# ProDoc_Home_Automation_Device_2026-02-15.net
KiCad netlist of a schematic drawn in EasyEDA Pro
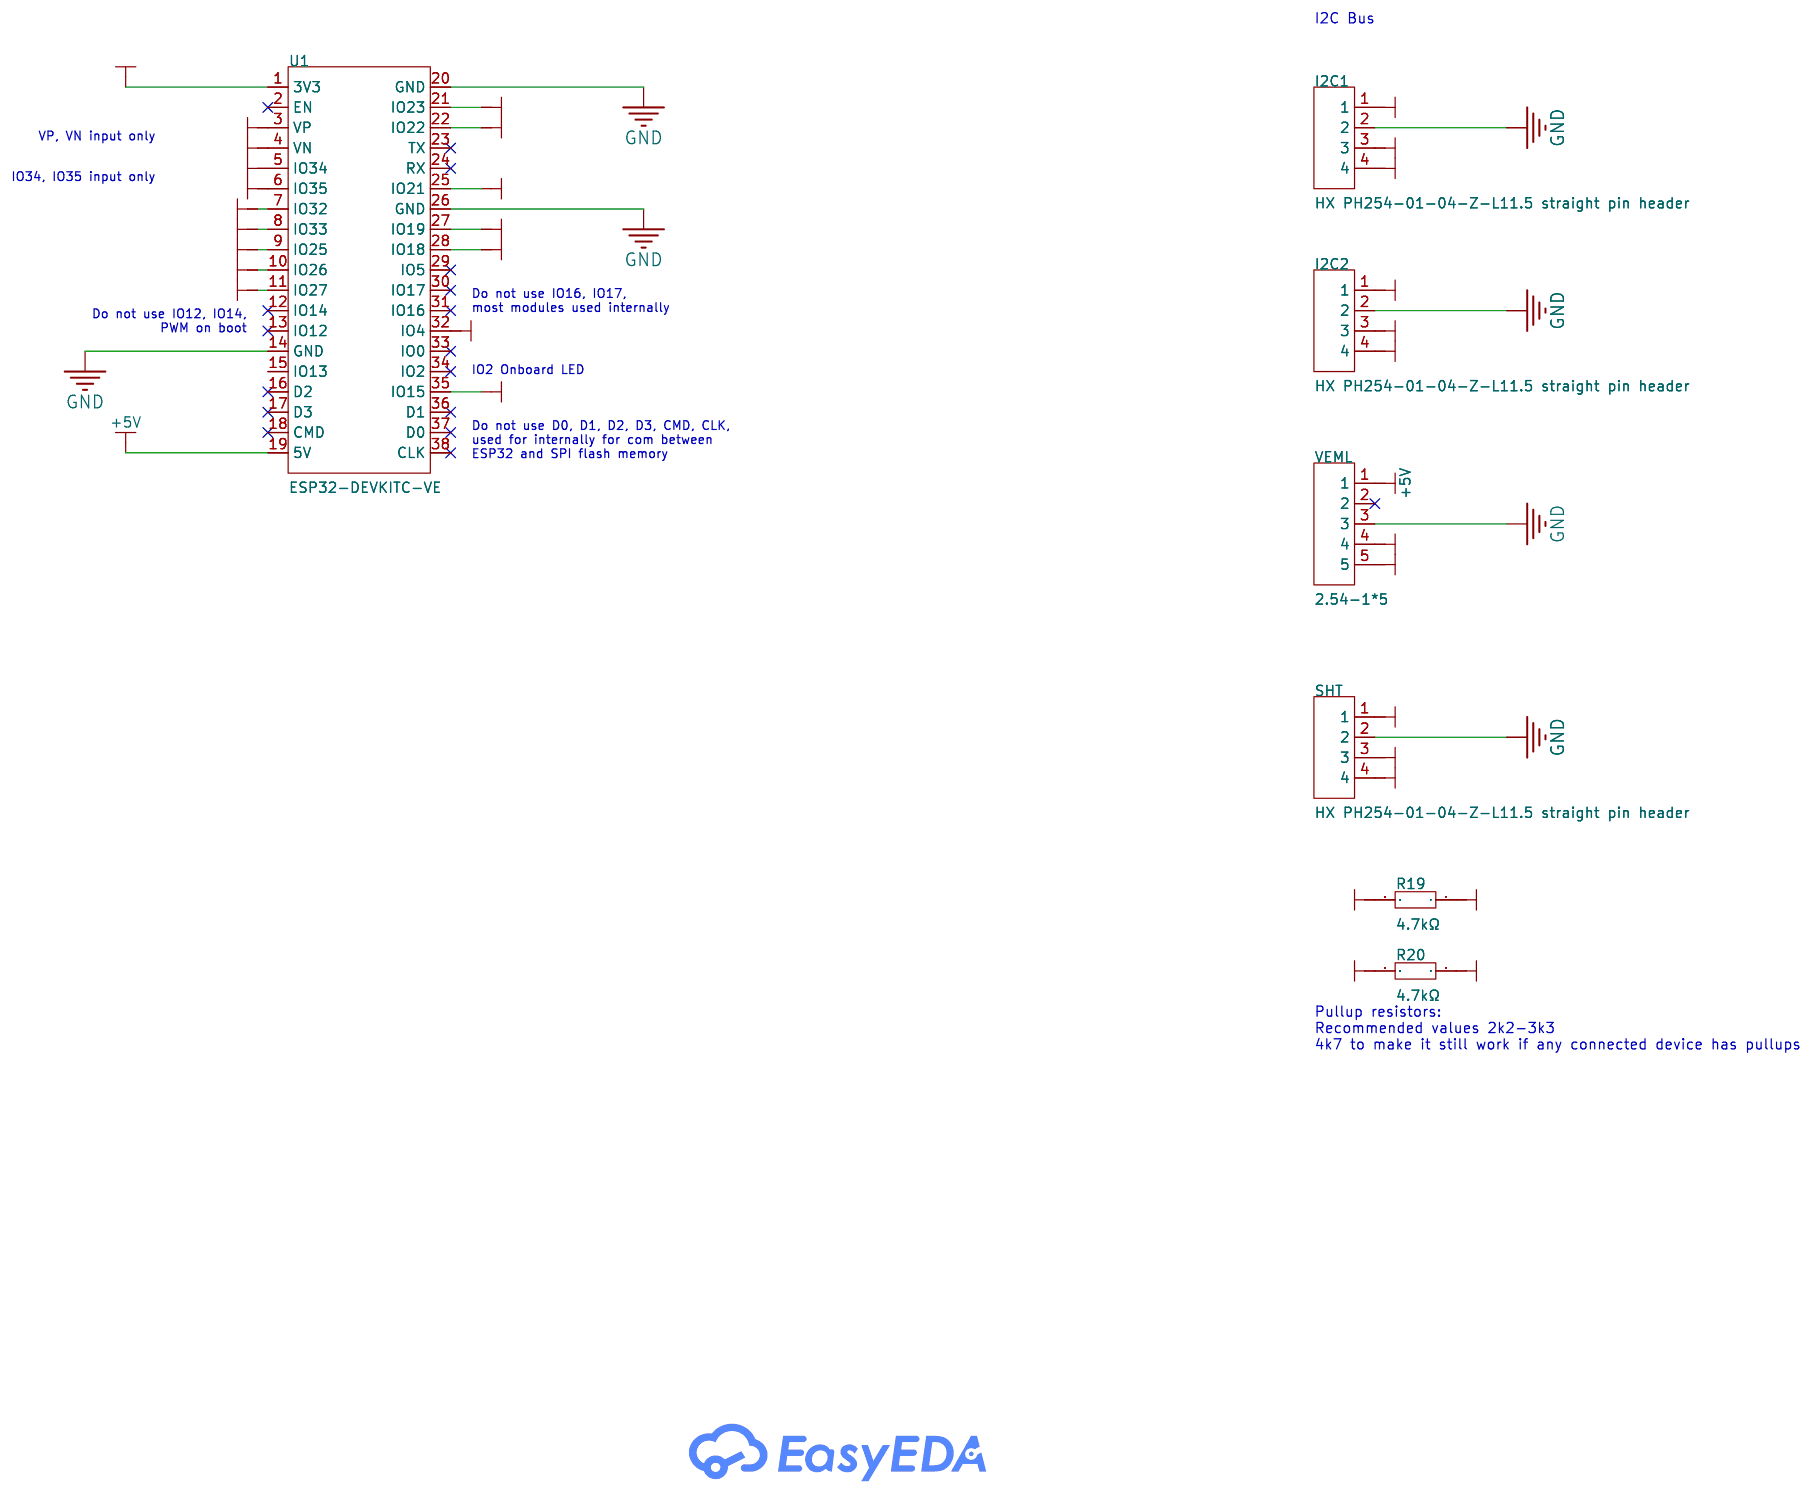
[diagram p0: Main]
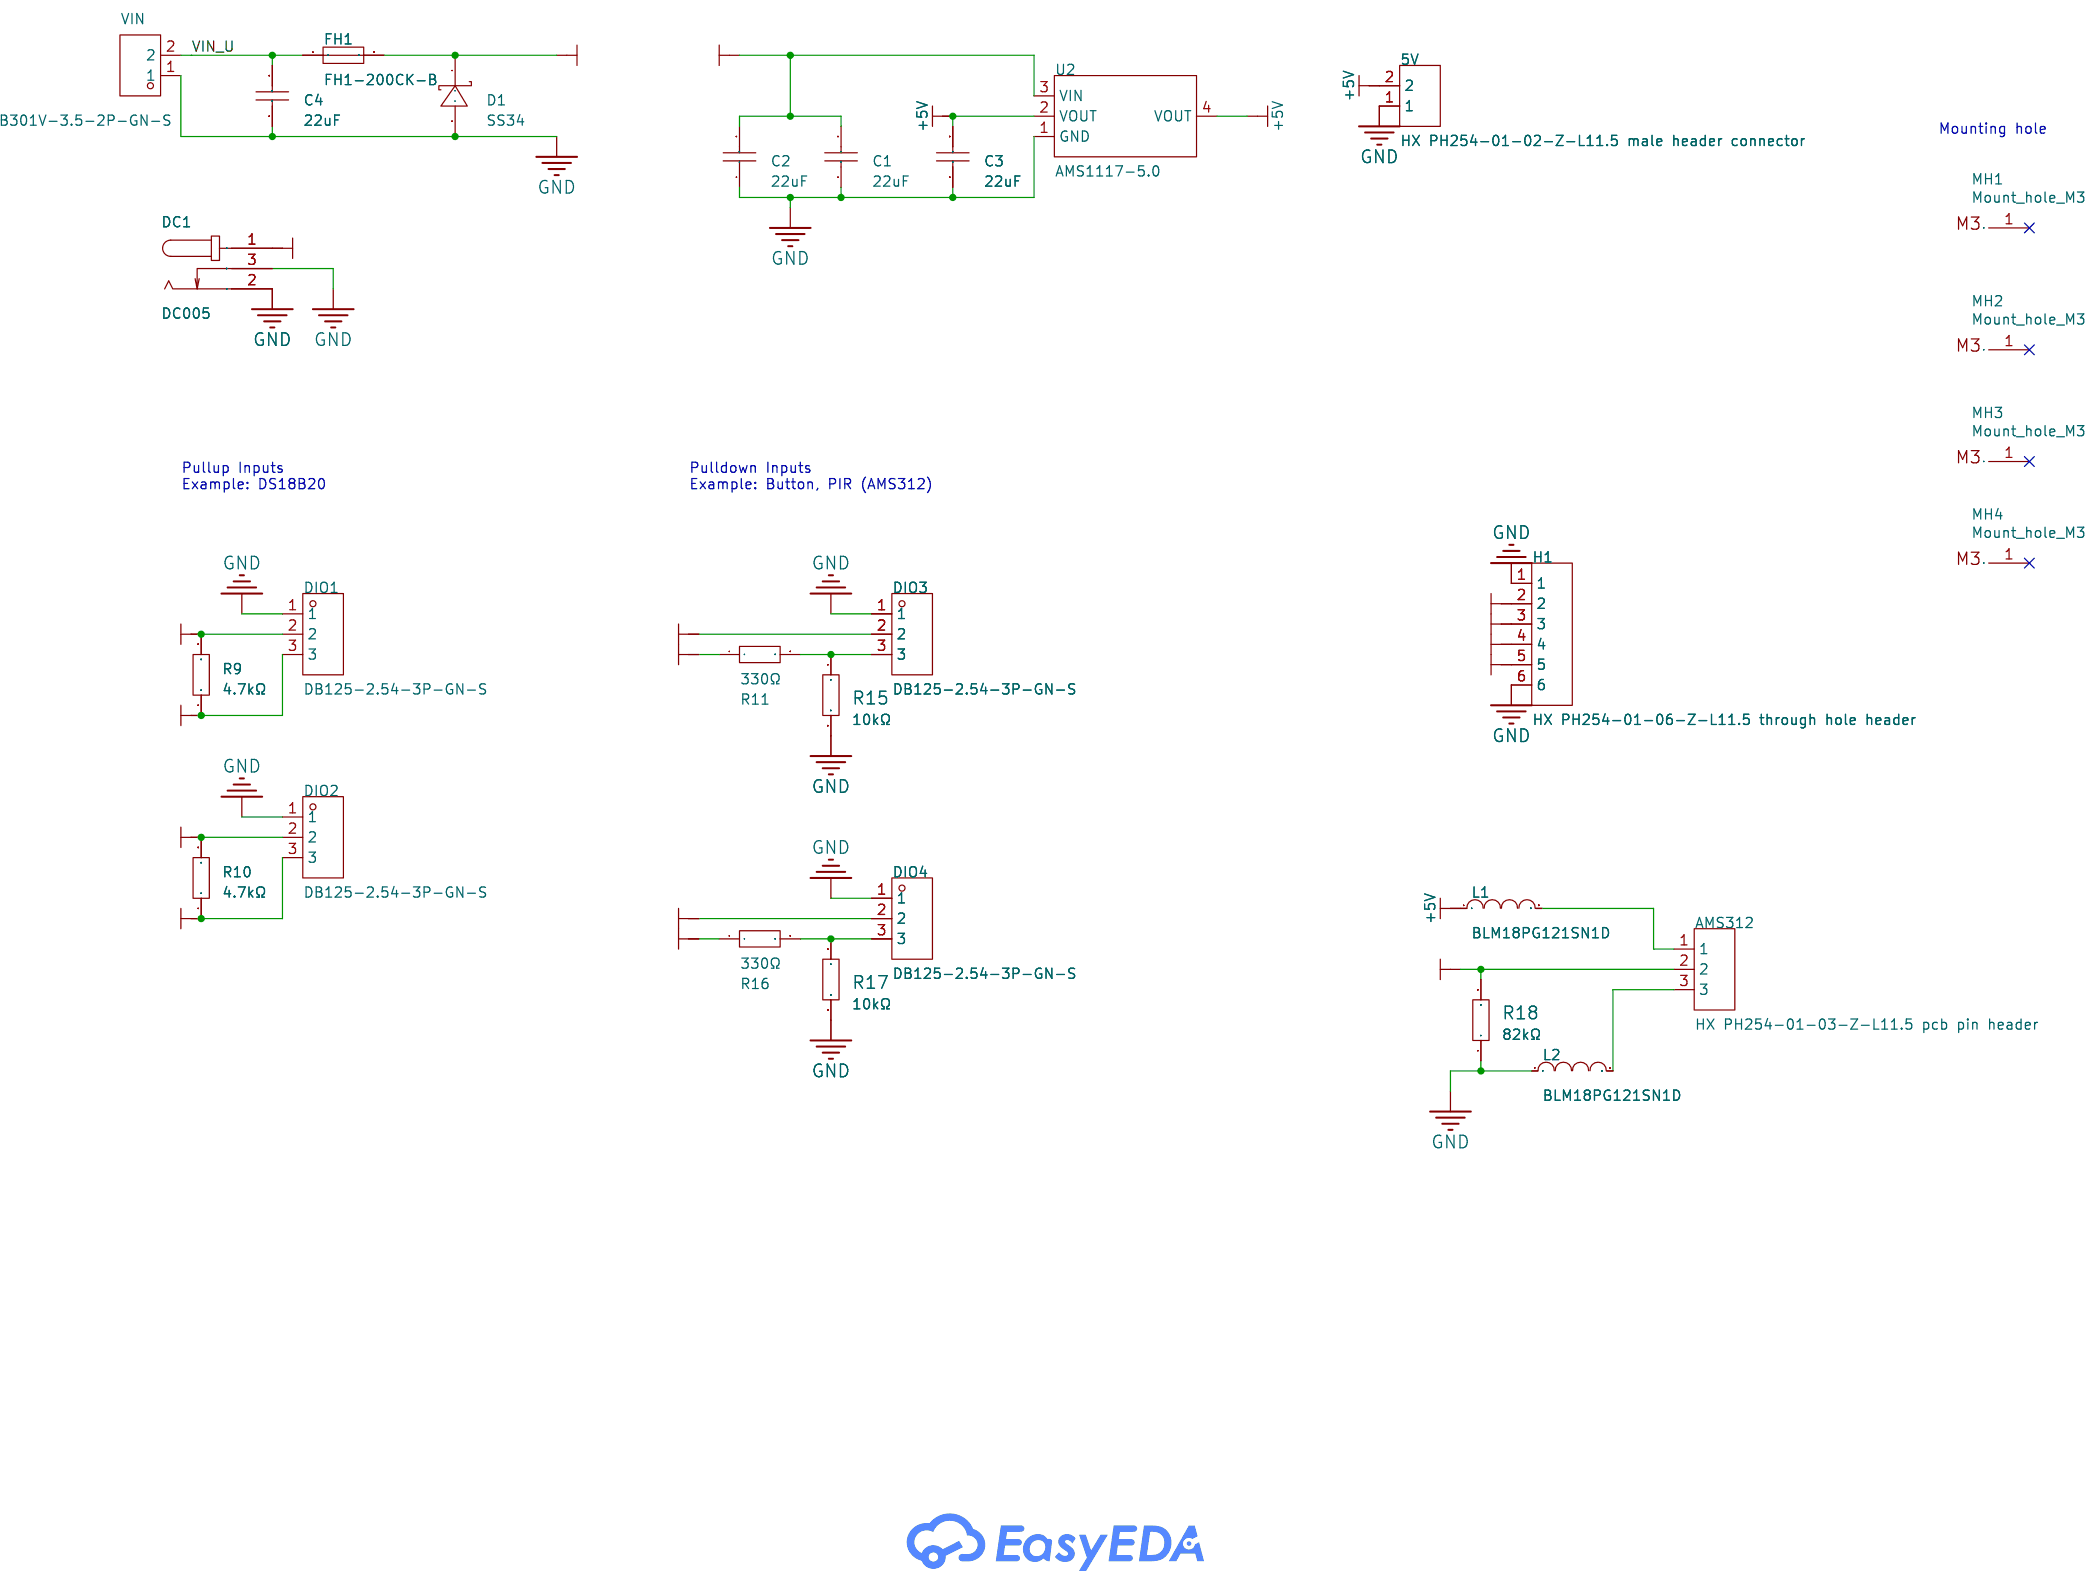
[diagram p1: Input and power]
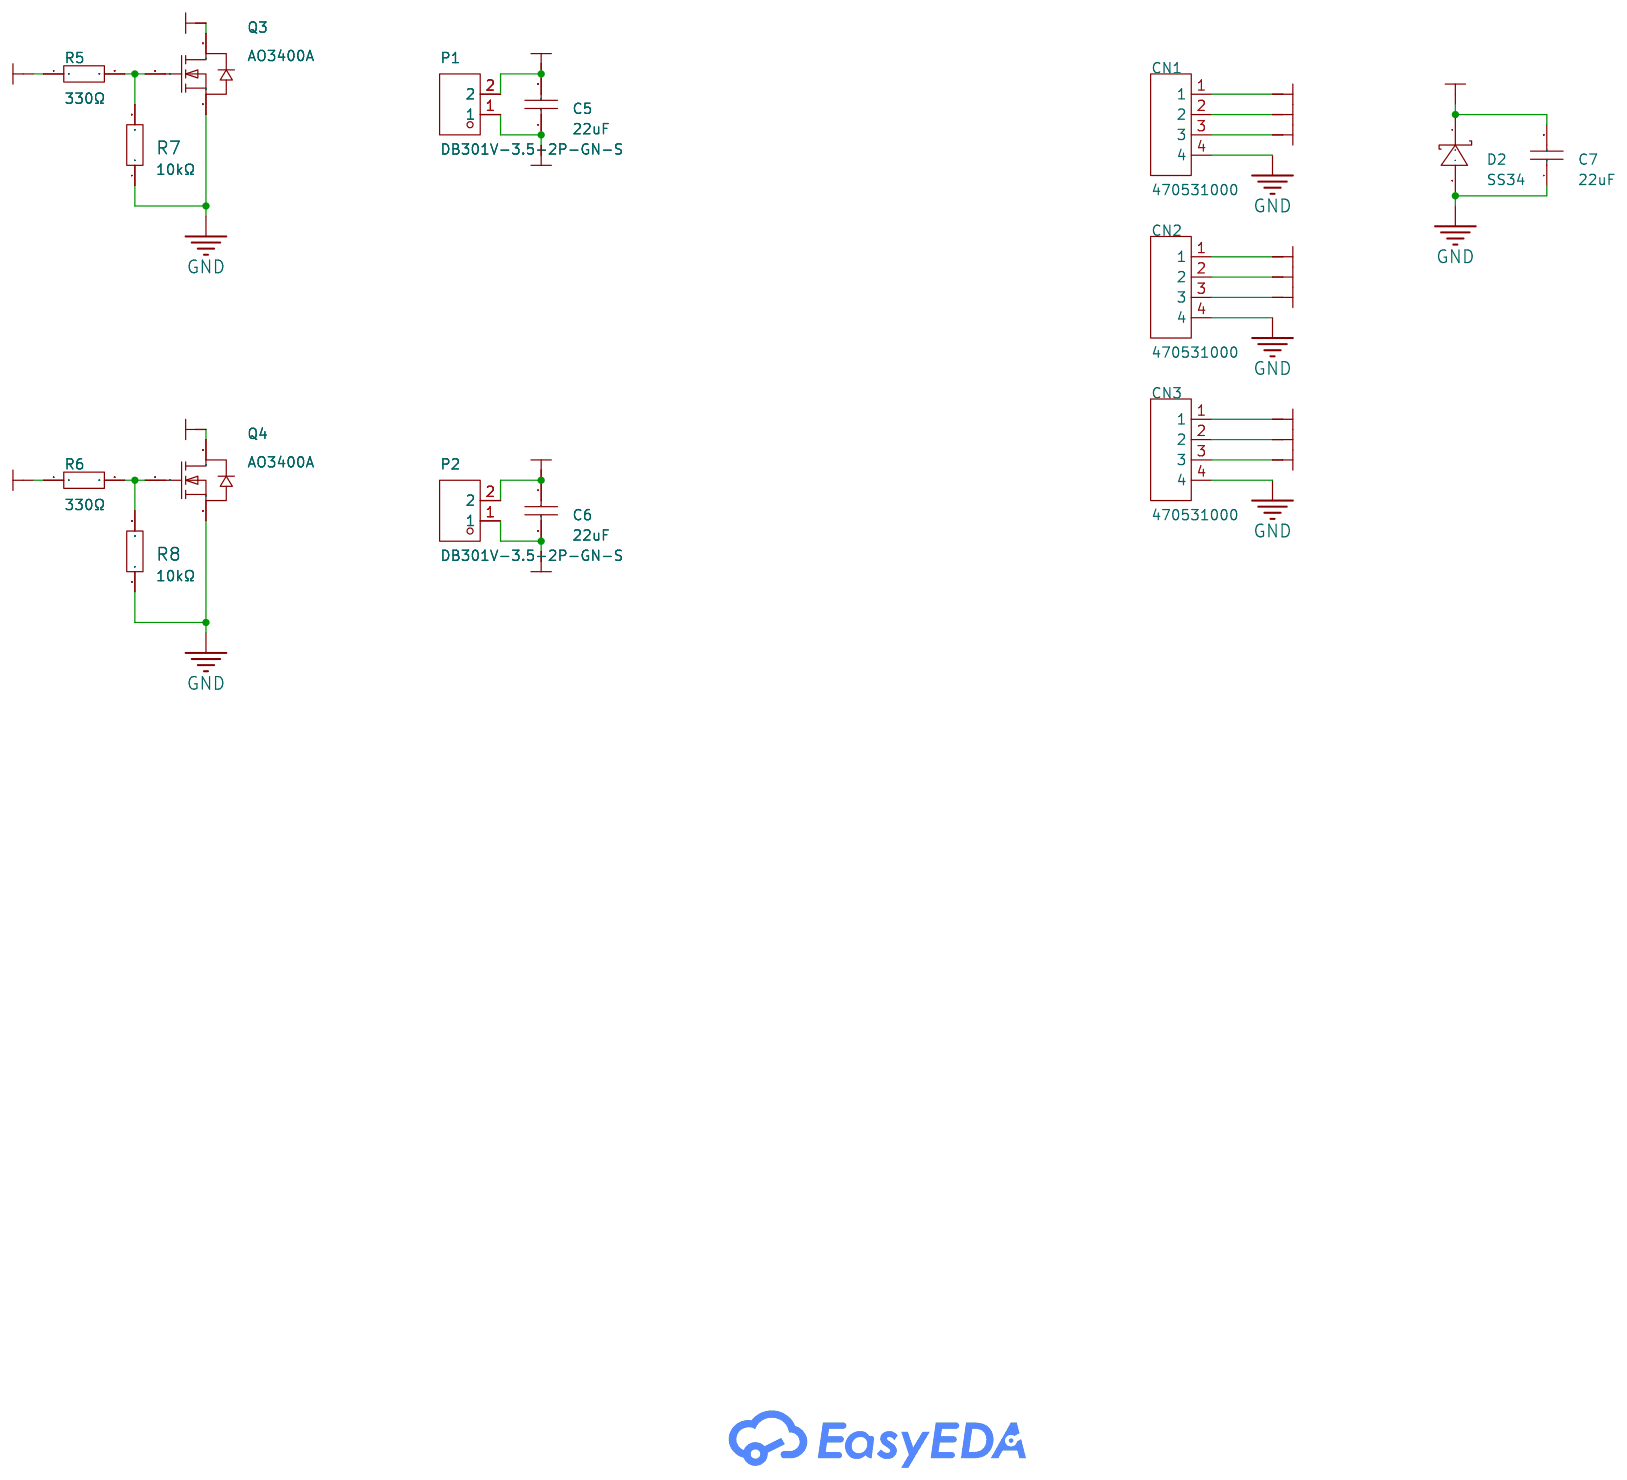
[diagram p2: Outputs]

(export (version "E")
  (design (tool "Eeschema 10.0.6"))
  (components
    (comp (ref "I2C1")
      (value "HX PH254-01-04-Z-L11.5 straight pin header")
      (footprint "easyedapro:HDR-TH_4P-HX-PH254-01-04-Z-L11.5")
      (fields (field (name "Manufacturer") "hanxia(韩下)"))
      (libsource (lib "easyedapro") (part "HX PH254-01-04-Z-L11.5 STRAIGHT PIN HEADER"))
    )
    (comp (ref "I2C2")
      (value "HX PH254-01-04-Z-L11.5 straight pin header")
      (footprint "easyedapro:HDR-TH_4P-HX-PH254-01-04-Z-L11.5")
      (fields (field (name "Manufacturer") "hanxia(韩下)"))
      (libsource (lib "easyedapro") (part "HX PH254-01-04-Z-L11.5 STRAIGHT PIN HEADER"))
    )
    (comp (ref "R19")
      (value "4.7kΩ")
      (footprint "easyedapro:R0603")
      (fields
        (field (name "Manufacturer Part") "0603WAF4701T5E")
        (field (name "Manufacturer") "UNI-ROYAL(厚声)")
      )
      (libsource (lib "easyedapro") (part "0603WAF4701T5E"))
    )
    (comp (ref "R20")
      (value "4.7kΩ")
      (footprint "easyedapro:R0603")
      (fields
        (field (name "Manufacturer Part") "0603WAF4701T5E")
        (field (name "Manufacturer") "UNI-ROYAL(厚声)")
      )
      (libsource (lib "easyedapro") (part "0603WAF4701T5E"))
    )
    (comp (ref "SHT")
      (value "HX PH254-01-04-Z-L11.5 straight pin header")
      (footprint "easyedapro:HDR-TH_4P-HX-PH254-01-04-Z-L11.5")
      (fields (field (name "Manufacturer") "hanxia(韩下)"))
      (libsource (lib "easyedapro") (part "HX PH254-01-04-Z-L11.5 STRAIGHT PIN HEADER"))
    )
    (comp (ref "U1")
      (value "ESP32-DEVKITC-VE")
      (footprint "easyedapro:BULETM-SMD_ESP32-DEVKITC")
      (fields (field (name "Manufacturer") "ESPRESSIF(乐鑫)"))
      (libsource (lib "easyedapro") (part "ESP32-DEVKITC-VE"))
    )
    (comp (ref "VEML")
      (value "2.54-1*5")
      (footprint "easyedapro:HDR-TH_5P-P2.54-V-M")
      (fields (field (name "Manufacturer") "ZHOURI(洲日)"))
      (libsource (lib "easyedapro") (part "2.54-1*5"))
    )
    (comp (ref "5V")
      (value "HX PH254-01-02-Z-L11.5 male header connector")
      (footprint "easyedapro:HDR-TH_2P-P2.54-V-M")
      (fields (field (name "Manufacturer") "hanxia(韩下)"))
      (libsource (lib "easyedapro") (part "HX PH254-01-02-Z-L11.5 MALE HEADER CONNECTOR"))
    )
    (comp (ref "AMS312")
      (value "HX PH254-01-03-Z-L11.5 pcb pin header")
      (footprint "easyedapro:HDR-TH_3P-P2.54-V-M-1")
      (fields (field (name "Manufacturer") "hanxia(韩下)"))
      (libsource (lib "easyedapro") (part "HX PH254-01-03-Z-L11.5 PCB PIN HEADER"))
    )
    (comp (ref "C1")
      (value "22uF")
      (footprint "easyedapro:C1206")
      (description "Capacitance:22uF Tolerance:±10% Tolerance:±10% Voltage Rating:25V Temperature Coefficient:X5R")
      (fields
        (field (name "Manufacturer Part") "CL31A226KAHNNNE")
        (field (name "Manufacturer") "SAMSUNG(三星)")
      )
      (libsource (lib "easyedapro") (part "CL31A226KAHNNNE"))
    )
    (comp (ref "C2")
      (value "22uF")
      (footprint "easyedapro:C1206")
      (description "Capacitance:22uF Tolerance:±10% Tolerance:±10% Voltage Rating:25V Temperature Coefficient:X5R")
      (fields
        (field (name "Manufacturer Part") "CL31A226KAHNNNE")
        (field (name "Manufacturer") "SAMSUNG(三星)")
      )
      (libsource (lib "easyedapro") (part "CL31A226KAHNNNE"))
    )
    (comp (ref "C3")
      (value "22uF")
      (footprint "easyedapro:C1206")
      (description "Capacitance:22uF Tolerance:±10% Tolerance:±10% Voltage Rating:25V Temperature Coefficient:X5R")
      (fields
        (field (name "Manufacturer Part") "CL31A226KAHNNNE")
        (field (name "Manufacturer") "SAMSUNG(三星)")
      )
      (libsource (lib "easyedapro") (part "CL31A226KAHNNNE"))
    )
    (comp (ref "C4")
      (value "22uF")
      (footprint "easyedapro:C1206")
      (description "Capacitance:22uF Tolerance:±10% Tolerance:±10% Voltage Rating:25V Temperature Coefficient:X5R")
      (fields
        (field (name "Manufacturer Part") "CL31A226KAHNNNE")
        (field (name "Manufacturer") "SAMSUNG(三星)")
      )
      (libsource (lib "easyedapro") (part "CL31A226KAHNNNE"))
    )
    (comp (ref "D1")
      (value "SS34")
      (footprint "easyedapro:SMA_L4.3-W2.6-LS5.2-RD")
      (fields (field (name "Manufacturer") "MDD(辰达半导体)"))
      (libsource (lib "easyedapro") (part "SS34_C8678"))
    )
    (comp (ref "DC1")
      (value "DC005")
      (footprint "easyedapro:DC-IN-TH_DC005")
      (fields (field (name "Manufacturer") "SHOU HAN(首韩)"))
      (libsource (lib "easyedapro") (part "DC005_C431533"))
    )
    (comp (ref "DIO1")
      (value "DB125-2.54-3P-GN-S")
      (footprint "easyedapro:CONN-TH_DB125-2.54-3P-GN")
      (fields (field (name "Manufacturer") "DORABO(地博电气)"))
      (libsource (lib "easyedapro") (part "DB125-2.54-3P-GN"))
    )
    (comp (ref "DIO2")
      (value "DB125-2.54-3P-GN-S")
      (footprint "easyedapro:CONN-TH_DB125-2.54-3P-GN")
      (fields (field (name "Manufacturer") "DORABO(地博电气)"))
      (libsource (lib "easyedapro") (part "DB125-2.54-3P-GN"))
    )
    (comp (ref "DIO3")
      (value "DB125-2.54-3P-GN-S")
      (footprint "easyedapro:CONN-TH_DB125-2.54-3P-GN")
      (fields (field (name "Manufacturer") "DORABO(地博电气)"))
      (libsource (lib "easyedapro") (part "DB125-2.54-3P-GN"))
    )
    (comp (ref "DIO4")
      (value "DB125-2.54-3P-GN-S")
      (footprint "easyedapro:CONN-TH_DB125-2.54-3P-GN")
      (fields (field (name "Manufacturer") "DORABO(地博电气)"))
      (libsource (lib "easyedapro") (part "DB125-2.54-3P-GN"))
    )
    (comp (ref "FH1")
      (value "FH1-200CK-B")
      (footprint "easyedapro:FUSE-TH_L24.8-W9.8-P22.60")
      (fields (field (name "Manufacturer") "HONGJU(宏聚)"))
      (libsource (lib "easyedapro") (part "FH1-200CK-B"))
    )
    (comp (ref "H1")
      (value "HX PH254-01-06-Z-L11.5 through hole header")
      (footprint "easyedapro:HDR-TH_6P-P2.54-V-M")
      (fields (field (name "Manufacturer") "hanxia(韩下)"))
      (libsource (lib "easyedapro") (part "HX PH254-01-06-Z-L11.5 THROUGH HOLE HEADER"))
    )
    (comp (ref "L1")
      (value "BLM18PG121SN1D")
      (footprint "easyedapro:L0603")
      (fields (field (name "Manufacturer") "muRata(村田)"))
      (libsource (lib "easyedapro") (part "BLM18PG121SN1D_C14709"))
    )
    (comp (ref "L2")
      (value "BLM18PG121SN1D")
      (footprint "easyedapro:L0603")
      (fields (field (name "Manufacturer") "muRata(村田)"))
      (libsource (lib "easyedapro") (part "BLM18PG121SN1D_C14709"))
    )
    (comp (ref "MH1")
      (value "Mount_hole_M3")
      (footprint "easyedapro:M3_MOUNTING_HOLE_REGULAR")
      (fields (field (name "Contributor") "sjvdmarel"))
      (libsource (lib "easyedapro") (part "Mount_hole_M3"))
    )
    (comp (ref "MH2")
      (value "Mount_hole_M3")
      (footprint "easyedapro:M3_MOUNTING_HOLE_REGULAR")
      (fields (field (name "Contributor") "sjvdmarel"))
      (libsource (lib "easyedapro") (part "Mount_hole_M3"))
    )
    (comp (ref "MH3")
      (value "Mount_hole_M3")
      (footprint "easyedapro:M3_MOUNTING_HOLE_REGULAR")
      (fields (field (name "Contributor") "sjvdmarel"))
      (libsource (lib "easyedapro") (part "Mount_hole_M3"))
    )
    (comp (ref "MH4")
      (value "Mount_hole_M3")
      (footprint "easyedapro:M3_MOUNTING_HOLE_REGULAR")
      (fields (field (name "Contributor") "sjvdmarel"))
      (libsource (lib "easyedapro") (part "Mount_hole_M3"))
    )
    (comp (ref "R9")
      (value "4.7kΩ")
      (footprint "easyedapro:R0603")
      (fields
        (field (name "Manufacturer Part") "0603WAF4701T5E")
        (field (name "Manufacturer") "UNI-ROYAL(厚声)")
      )
      (libsource (lib "easyedapro") (part "0603WAF4701T5E"))
    )
    (comp (ref "R10")
      (value "4.7kΩ")
      (footprint "easyedapro:R0603")
      (fields
        (field (name "Manufacturer Part") "0603WAF4701T5E")
        (field (name "Manufacturer") "UNI-ROYAL(厚声)")
      )
      (libsource (lib "easyedapro") (part "0603WAF4701T5E"))
    )
    (comp (ref "R11")
      (value "330Ω")
      (footprint "easyedapro:R0603")
      (fields
        (field (name "Manufacturer Part") "0603WAF3300T5E")
        (field (name "Manufacturer") "UNI-ROYAL(厚声)")
      )
      (libsource (lib "easyedapro") (part "0603WAF3300T5E"))
    )
    (comp (ref "R15")
      (value "10kΩ")
      (footprint "easyedapro:R0603")
      (fields
        (field (name "Manufacturer Part") "0603WAF1002T5E")
        (field (name "Manufacturer") "UNI-ROYAL(厚声)")
      )
      (libsource (lib "easyedapro") (part "0603WAF1002T5E"))
    )
    (comp (ref "R16")
      (value "330Ω")
      (footprint "easyedapro:R0603")
      (fields
        (field (name "Manufacturer Part") "0603WAF3300T5E")
        (field (name "Manufacturer") "UNI-ROYAL(厚声)")
      )
      (libsource (lib "easyedapro") (part "0603WAF3300T5E"))
    )
    (comp (ref "R17")
      (value "10kΩ")
      (footprint "easyedapro:R0603")
      (fields
        (field (name "Manufacturer Part") "0603WAF1002T5E")
        (field (name "Manufacturer") "UNI-ROYAL(厚声)")
      )
      (libsource (lib "easyedapro") (part "0603WAF1002T5E"))
    )
    (comp (ref "R18")
      (value "82kΩ")
      (footprint "easyedapro:R0603")
      (fields
        (field (name "Manufacturer Part") "0603WAF8202T5E")
        (field (name "Manufacturer") "UNI-ROYAL(厚声)")
      )
      (libsource (lib "easyedapro") (part "0603WAF8202T5E"))
    )
    (comp (ref "U2")
      (value "AMS1117-5.0")
      (footprint "easyedapro:SOT-223_L6.5-W3.5-P2.30-LS7.0-BR")
      (fields (field (name "Manufacturer") "AMS"))
      (libsource (lib "easyedapro") (part "AMS1117-5.0"))
    )
    (comp (ref "VIN")
      (value "DB301V-3.5-2P-GN-S")
      (footprint "easyedapro:CONN-TH_DB301V-3.5-2P-GN")
      (fields (field (name "Manufacturer") "DORABO(地博电气)"))
      (libsource (lib "easyedapro") (part "DB301V-3.5-2P-GN"))
    )
    (comp (ref "C5")
      (value "22uF")
      (footprint "easyedapro:C1206")
      (description "Capacitance:22uF Tolerance:±10% Tolerance:±10% Voltage Rating:25V Temperature Coefficient:X5R")
      (fields
        (field (name "Manufacturer Part") "CL31A226KAHNNNE")
        (field (name "Manufacturer") "SAMSUNG(三星)")
      )
      (libsource (lib "easyedapro") (part "CL31A226KAHNNNE"))
    )
    (comp (ref "C6")
      (value "22uF")
      (footprint "easyedapro:C1206")
      (description "Capacitance:22uF Tolerance:±10% Tolerance:±10% Voltage Rating:25V Temperature Coefficient:X5R")
      (fields
        (field (name "Manufacturer Part") "CL31A226KAHNNNE")
        (field (name "Manufacturer") "SAMSUNG(三星)")
      )
      (libsource (lib "easyedapro") (part "CL31A226KAHNNNE"))
    )
    (comp (ref "C7")
      (value "22uF")
      (footprint "easyedapro:C1206")
      (description "Capacitance:22uF Tolerance:±10% Tolerance:±10% Voltage Rating:25V Temperature Coefficient:X5R")
      (fields
        (field (name "Manufacturer Part") "CL31A226KAHNNNE")
        (field (name "Manufacturer") "SAMSUNG(三星)")
      )
      (libsource (lib "easyedapro") (part "CL31A226KAHNNNE"))
    )
    (comp (ref "CN1")
      (value "470531000")
      (footprint "easyedapro:CONN-TH_4P-P2.54_0470531000")
      (fields (field (name "Manufacturer") "MOLEX"))
      (libsource (lib "easyedapro") (part "0470531000"))
    )
    (comp (ref "CN2")
      (value "470531000")
      (footprint "easyedapro:CONN-TH_4P-P2.54_0470531000")
      (fields (field (name "Manufacturer") "MOLEX"))
      (libsource (lib "easyedapro") (part "0470531000"))
    )
    (comp (ref "CN3")
      (value "470531000")
      (footprint "easyedapro:CONN-TH_4P-P2.54_0470531000")
      (fields (field (name "Manufacturer") "MOLEX"))
      (libsource (lib "easyedapro") (part "0470531000"))
    )
    (comp (ref "D2")
      (value "SS34")
      (footprint "easyedapro:SMA_L4.3-W2.6-LS5.2-RD")
      (fields (field (name "Manufacturer") "MDD(辰达半导体)"))
      (libsource (lib "easyedapro") (part "SS34_C8678"))
    )
    (comp (ref "P1")
      (value "DB301V-3.5-2P-GN-S")
      (footprint "easyedapro:CONN-TH_DB301V-3.5-2P-GN")
      (fields (field (name "Manufacturer") "DORABO(地博电气)"))
      (libsource (lib "easyedapro") (part "DB301V-3.5-2P-GN"))
    )
    (comp (ref "P2")
      (value "DB301V-3.5-2P-GN-S")
      (footprint "easyedapro:CONN-TH_DB301V-3.5-2P-GN")
      (fields (field (name "Manufacturer") "DORABO(地博电气)"))
      (libsource (lib "easyedapro") (part "DB301V-3.5-2P-GN"))
    )
    (comp (ref "Q3")
      (value "AO3400A")
      (footprint "easyedapro:SOT-23-3_L2.9-W1.3-P1.90-LS2.4-BR")
      (fields (field (name "Manufacturer") "AOS"))
      (libsource (lib "easyedapro") (part "AO3400A"))
    )
    (comp (ref "Q4")
      (value "AO3400A")
      (footprint "easyedapro:SOT-23-3_L2.9-W1.3-P1.90-LS2.4-BR")
      (fields (field (name "Manufacturer") "AOS"))
      (libsource (lib "easyedapro") (part "AO3400A"))
    )
    (comp (ref "R5")
      (value "330Ω")
      (footprint "easyedapro:R0603")
      (fields
        (field (name "Manufacturer Part") "0603WAF3300T5E")
        (field (name "Manufacturer") "UNI-ROYAL(厚声)")
      )
      (libsource (lib "easyedapro") (part "0603WAF3300T5E"))
    )
    (comp (ref "R6")
      (value "330Ω")
      (footprint "easyedapro:R0603")
      (fields
        (field (name "Manufacturer Part") "0603WAF3300T5E")
        (field (name "Manufacturer") "UNI-ROYAL(厚声)")
      )
      (libsource (lib "easyedapro") (part "0603WAF3300T5E"))
    )
    (comp (ref "R7")
      (value "10kΩ")
      (footprint "easyedapro:R0603")
      (fields
        (field (name "Manufacturer Part") "0603WAF1002T5E")
        (field (name "Manufacturer") "UNI-ROYAL(厚声)")
      )
      (libsource (lib "easyedapro") (part "0603WAF1002T5E"))
    )
    (comp (ref "R8")
      (value "10kΩ")
      (footprint "easyedapro:R0603")
      (fields
        (field (name "Manufacturer Part") "0603WAF1002T5E")
        (field (name "Manufacturer") "UNI-ROYAL(厚声)")
      )
      (libsource (lib "easyedapro") (part "0603WAF1002T5E"))
    )
  )
  (nets
    (net (code "1") (name "+3V3") (class "Default")
      (node (ref "DIO1") (pin "2") (pinfunction "2_2") (pintype "unspecified"))
      (node (ref "DIO2") (pin "2") (pinfunction "2_2") (pintype "unspecified"))
      (node (ref "DIO3") (pin "2") (pinfunction "2_2") (pintype "unspecified"))
      (node (ref "DIO4") (pin "2") (pinfunction "2_2") (pintype "unspecified"))
      (node (ref "H1") (pin "5") (pinfunction "5_5") (pintype "unspecified"))
      (node (ref "I2C1") (pin "1") (pinfunction "1_1") (pintype "unspecified"))
      (node (ref "I2C2") (pin "1") (pinfunction "1_1") (pintype "unspecified"))
      (node (ref "R10") (pin "2") (pinfunction "2_2") (pintype "input"))
      (node (ref "R19") (pin "2") (pinfunction "2_2") (pintype "input"))
      (node (ref "R20") (pin "2") (pinfunction "2_2") (pintype "input"))
      (node (ref "R9") (pin "2") (pinfunction "2_2") (pintype "input"))
      (node (ref "SHT") (pin "1") (pinfunction "1_1") (pintype "unspecified"))
      (node (ref "U1") (pin "1") (pinfunction "3V3_1") (pintype "unspecified"))
    )
    (net (code "2") (name "+5V") (class "Default")
      (node (ref "5V") (pin "2") (pinfunction "2_2") (pintype "unspecified"))
      (node (ref "C3") (pin "2") (pinfunction "2_2") (pintype "input"))
      (node (ref "L1") (pin "1") (pinfunction "1_1") (pintype "unspecified"))
      (node (ref "U1") (pin "19") (pinfunction "5V_19") (pintype "unspecified"))
      (node (ref "U2") (pin "2") (pinfunction "VOUT_2") (pintype "unspecified"))
      (node (ref "U2") (pin "4") (pinfunction "VOUT_4") (pintype "unspecified"))
      (node (ref "VEML") (pin "1") (pinfunction "1_1") (pintype "unspecified"))
    )
    (net (code "3") (name "DIO1S") (class "Default")
      (node (ref "DIO1") (pin "3") (pinfunction "3_3") (pintype "unspecified"))
      (node (ref "R9") (pin "1") (pinfunction "1_1") (pintype "input"))
      (node (ref "U1") (pin "7") (pinfunction "IO32_7") (pintype "unspecified"))
    )
    (net (code "4") (name "DIO2S") (class "Default")
      (node (ref "DIO2") (pin "3") (pinfunction "3_3") (pintype "unspecified"))
      (node (ref "R10") (pin "1") (pinfunction "1_1") (pintype "input"))
      (node (ref "U1") (pin "8") (pinfunction "IO33_8") (pintype "unspecified"))
    )
    (net (code "5") (name "DIO3S") (class "Default")
      (node (ref "R11") (pin "1") (pinfunction "1_1") (pintype "input"))
      (node (ref "U1") (pin "21") (pinfunction "IO23_21") (pintype "unspecified"))
    )
    (net (code "6") (name "DIO4S") (class "Default")
      (node (ref "R16") (pin "1") (pinfunction "1_1") (pintype "input"))
      (node (ref "U1") (pin "35") (pinfunction "IO15_35") (pintype "unspecified"))
    )
    (net (code "7") (name "DI_AMS") (class "Default")
      (node (ref "AMS312") (pin "2") (pinfunction "2_2") (pintype "unspecified"))
      (node (ref "R18") (pin "2") (pinfunction "2_2") (pintype "input"))
      (node (ref "U1") (pin "5") (pinfunction "IO34_5") (pintype "unspecified"))
    )
    (net (code "8") (name "EXP2") (class "Default")
      (node (ref "H1") (pin "2") (pinfunction "2_2") (pintype "unspecified"))
      (node (ref "U1") (pin "6") (pinfunction "IO35_6") (pintype "unspecified"))
    )
    (net (code "9") (name "EXP3") (class "Default")
      (node (ref "H1") (pin "3") (pinfunction "3_3") (pintype "unspecified"))
      (node (ref "U1") (pin "3") (pinfunction "VP_3") (pintype "unspecified"))
    )
    (net (code "10") (name "EXP4") (class "Default")
      (node (ref "H1") (pin "4") (pinfunction "4_4") (pintype "unspecified"))
      (node (ref "U1") (pin "4") (pinfunction "VN_4") (pintype "unspecified"))
    )
    (net (code "11") (name "FAN_FB1") (class "Default")
      (node (ref "CN1") (pin "2") (pinfunction "2_2") (pintype "unspecified"))
      (node (ref "U1") (pin "9") (pinfunction "IO25_9") (pintype "unspecified"))
    )
    (net (code "12") (name "FAN_FB2") (class "Default")
      (node (ref "CN2") (pin "2") (pinfunction "2_2") (pintype "unspecified"))
      (node (ref "U1") (pin "10") (pinfunction "IO26_10") (pintype "unspecified"))
    )
    (net (code "13") (name "FAN_FB3") (class "Default")
      (node (ref "CN3") (pin "2") (pinfunction "2_2") (pintype "unspecified"))
      (node (ref "U1") (pin "11") (pinfunction "IO27_11") (pintype "unspecified"))
    )
    (net (code "14") (name "FAN_PWM") (class "Default")
      (node (ref "CN1") (pin "1") (pinfunction "1_1") (pintype "unspecified"))
      (node (ref "CN2") (pin "1") (pinfunction "1_1") (pintype "unspecified"))
      (node (ref "CN3") (pin "1") (pinfunction "1_1") (pintype "unspecified"))
      (node (ref "U1") (pin "32") (pinfunction "IO4_32") (pintype "unspecified"))
    )
    (net (code "15") (name "GND") (class "Default")
      (node (ref "5V") (pin "1") (pinfunction "1_1") (pintype "unspecified"))
      (node (ref "C1") (pin "1") (pinfunction "1_1") (pintype "input"))
      (node (ref "C2") (pin "1") (pinfunction "1_1") (pintype "input"))
      (node (ref "C3") (pin "1") (pinfunction "1_1") (pintype "input"))
      (node (ref "C4") (pin "1") (pinfunction "1_1") (pintype "input"))
      (node (ref "C7") (pin "1") (pinfunction "1_1") (pintype "input"))
      (node (ref "CN1") (pin "4") (pinfunction "4_4") (pintype "unspecified"))
      (node (ref "CN2") (pin "4") (pinfunction "4_4") (pintype "unspecified"))
      (node (ref "CN3") (pin "4") (pinfunction "4_4") (pintype "unspecified"))
      (node (ref "D1") (pin "2") (pinfunction "A_2") (pintype "unspecified"))
      (node (ref "D2") (pin "2") (pinfunction "A_2") (pintype "unspecified"))
      (node (ref "DC1") (pin "2") (pinfunction "2_2") (pintype "unspecified"))
      (node (ref "DC1") (pin "3") (pinfunction "3_3") (pintype "unspecified"))
      (node (ref "DIO1") (pin "1") (pinfunction "1_1") (pintype "unspecified"))
      (node (ref "DIO2") (pin "1") (pinfunction "1_1") (pintype "unspecified"))
      (node (ref "DIO3") (pin "1") (pinfunction "1_1") (pintype "unspecified"))
      (node (ref "DIO4") (pin "1") (pinfunction "1_1") (pintype "unspecified"))
      (node (ref "H1") (pin "1") (pinfunction "1_1") (pintype "unspecified"))
      (node (ref "H1") (pin "6") (pinfunction "6_6") (pintype "unspecified"))
      (node (ref "I2C1") (pin "2") (pinfunction "2_2") (pintype "unspecified"))
      (node (ref "I2C2") (pin "2") (pinfunction "2_2") (pintype "unspecified"))
      (node (ref "L2") (pin "1") (pinfunction "1_1") (pintype "unspecified"))
      (node (ref "Q3") (pin "2") (pinfunction "S_2") (pintype "unspecified"))
      (node (ref "Q4") (pin "2") (pinfunction "S_2") (pintype "unspecified"))
      (node (ref "R15") (pin "2") (pinfunction "2_2") (pintype "input"))
      (node (ref "R17") (pin "2") (pinfunction "2_2") (pintype "input"))
      (node (ref "R18") (pin "1") (pinfunction "1_1") (pintype "input"))
      (node (ref "R7") (pin "1") (pinfunction "1_1") (pintype "input"))
      (node (ref "R8") (pin "1") (pinfunction "1_1") (pintype "input"))
      (node (ref "SHT") (pin "2") (pinfunction "2_2") (pintype "unspecified"))
      (node (ref "U1") (pin "14") (pinfunction "GND_14") (pintype "unspecified"))
      (node (ref "U1") (pin "20") (pinfunction "GND_20") (pintype "unspecified"))
      (node (ref "U1") (pin "26") (pinfunction "GND_26") (pintype "unspecified"))
      (node (ref "U2") (pin "1") (pinfunction "GND_1") (pintype "unspecified"))
      (node (ref "VEML") (pin "3") (pinfunction "3_3") (pintype "unspecified"))
      (node (ref "VIN") (pin "1") (pinfunction "1_1") (pintype "unspecified"))
    )
    (net (code "16") (name "Net-(AMS312-Pad1)") (class "Default")
      (node (ref "AMS312") (pin "1") (pinfunction "1_1") (pintype "unspecified"))
      (node (ref "L1") (pin "2") (pinfunction "2_2") (pintype "unspecified"))
    )
    (net (code "17") (name "Net-(AMS312-Pad3)") (class "Default")
      (node (ref "AMS312") (pin "3") (pinfunction "3_3") (pintype "unspecified"))
      (node (ref "L2") (pin "2") (pinfunction "2_2") (pintype "unspecified"))
    )
    (net (code "18") (name "Net-(DIO3-Pad3)") (class "Default")
      (node (ref "DIO3") (pin "3") (pinfunction "3_3") (pintype "unspecified"))
      (node (ref "R11") (pin "2") (pinfunction "2_2") (pintype "input"))
      (node (ref "R15") (pin "1") (pinfunction "1_1") (pintype "input"))
    )
    (net (code "19") (name "Net-(DIO4-Pad3)") (class "Default")
      (node (ref "DIO4") (pin "3") (pinfunction "3_3") (pintype "unspecified"))
      (node (ref "R16") (pin "2") (pinfunction "2_2") (pintype "input"))
      (node (ref "R17") (pin "1") (pinfunction "1_1") (pintype "input"))
    )
    (net (code "20") (name "Net-(Q3-G)") (class "Default")
      (node (ref "Q3") (pin "1") (pinfunction "G_1") (pintype "unspecified"))
      (node (ref "R5") (pin "2") (pinfunction "2_2") (pintype "input"))
      (node (ref "R7") (pin "2") (pinfunction "2_2") (pintype "input"))
    )
    (net (code "21") (name "Net-(Q4-G)") (class "Default")
      (node (ref "Q4") (pin "1") (pinfunction "G_1") (pintype "unspecified"))
      (node (ref "R6") (pin "2") (pinfunction "2_2") (pintype "input"))
      (node (ref "R8") (pin "2") (pinfunction "2_2") (pintype "input"))
    )
    (net (code "22") (name "P1P") (class "Default")
      (node (ref "C5") (pin "1") (pinfunction "1_1") (pintype "input"))
      (node (ref "P1") (pin "1") (pinfunction "1_1") (pintype "unspecified"))
      (node (ref "Q3") (pin "3") (pinfunction "D_3") (pintype "unspecified"))
    )
    (net (code "23") (name "P1S") (class "Default")
      (node (ref "R5") (pin "1") (pinfunction "1_1") (pintype "input"))
      (node (ref "U1") (pin "28") (pinfunction "IO18_28") (pintype "unspecified"))
    )
    (net (code "24") (name "P2P") (class "Default")
      (node (ref "C6") (pin "1") (pinfunction "1_1") (pintype "input"))
      (node (ref "P2") (pin "1") (pinfunction "1_1") (pintype "unspecified"))
      (node (ref "Q4") (pin "3") (pinfunction "D_3") (pintype "unspecified"))
    )
    (net (code "25") (name "P2S") (class "Default")
      (node (ref "R6") (pin "1") (pinfunction "1_1") (pintype "input"))
      (node (ref "U1") (pin "27") (pinfunction "IO19_27") (pintype "unspecified"))
    )
    (net (code "26") (name "SCL") (class "Default")
      (node (ref "I2C1") (pin "3") (pinfunction "3_3") (pintype "unspecified"))
      (node (ref "I2C2") (pin "3") (pinfunction "3_3") (pintype "unspecified"))
      (node (ref "R19") (pin "1") (pinfunction "1_1") (pintype "input"))
      (node (ref "SHT") (pin "3") (pinfunction "3_3") (pintype "unspecified"))
      (node (ref "U1") (pin "22") (pinfunction "IO22_22") (pintype "unspecified"))
      (node (ref "VEML") (pin "4") (pinfunction "4_4") (pintype "unspecified"))
    )
    (net (code "27") (name "SDA") (class "Default")
      (node (ref "I2C1") (pin "4") (pinfunction "4_4") (pintype "unspecified"))
      (node (ref "I2C2") (pin "4") (pinfunction "4_4") (pintype "unspecified"))
      (node (ref "R20") (pin "1") (pinfunction "1_1") (pintype "input"))
      (node (ref "SHT") (pin "4") (pinfunction "4_4") (pintype "unspecified"))
      (node (ref "U1") (pin "25") (pinfunction "IO21_25") (pintype "unspecified"))
      (node (ref "VEML") (pin "5") (pinfunction "5_5") (pintype "unspecified"))
    )
    (net (code "28") (name "VIN") (class "Default")
      (node (ref "C1") (pin "2") (pinfunction "2_2") (pintype "input"))
      (node (ref "C2") (pin "2") (pinfunction "2_2") (pintype "input"))
      (node (ref "C5") (pin "2") (pinfunction "2_2") (pintype "input"))
      (node (ref "C6") (pin "2") (pinfunction "2_2") (pintype "input"))
      (node (ref "C7") (pin "2") (pinfunction "2_2") (pintype "input"))
      (node (ref "CN1") (pin "3") (pinfunction "3_3") (pintype "unspecified"))
      (node (ref "CN2") (pin "3") (pinfunction "3_3") (pintype "unspecified"))
      (node (ref "CN3") (pin "3") (pinfunction "3_3") (pintype "unspecified"))
      (node (ref "D1") (pin "1") (pinfunction "K_1") (pintype "unspecified"))
      (node (ref "D2") (pin "1") (pinfunction "K_1") (pintype "unspecified"))
      (node (ref "FH1") (pin "2") (pinfunction "2_2") (pintype "unspecified"))
      (node (ref "P1") (pin "2") (pinfunction "2_2") (pintype "unspecified"))
      (node (ref "P2") (pin "2") (pinfunction "2_2") (pintype "unspecified"))
      (node (ref "U2") (pin "3") (pinfunction "VIN_3") (pintype "unspecified"))
    )
    (net (code "29") (name "VIN_U") (class "Default")
      (node (ref "C4") (pin "2") (pinfunction "2_2") (pintype "input"))
      (node (ref "DC1") (pin "1") (pinfunction "1_1") (pintype "unspecified"))
      (node (ref "FH1") (pin "1") (pinfunction "1_1") (pintype "unspecified"))
      (node (ref "VIN") (pin "2") (pinfunction "2_2") (pintype "unspecified"))
    )
    (net (code "30") (name "unconnected-(MH1-Pad1)") (class "Default")
      (node (ref "MH1") (pin "1") (pinfunction "1_1") (pintype "unspecified+no_connect"))
    )
    (net (code "31") (name "unconnected-(MH2-Pad1)") (class "Default")
      (node (ref "MH2") (pin "1") (pinfunction "1_1") (pintype "unspecified+no_connect"))
    )
    (net (code "32") (name "unconnected-(MH3-Pad1)") (class "Default")
      (node (ref "MH3") (pin "1") (pinfunction "1_1") (pintype "unspecified+no_connect"))
    )
    (net (code "33") (name "unconnected-(MH4-Pad1)") (class "Default")
      (node (ref "MH4") (pin "1") (pinfunction "1_1") (pintype "unspecified+no_connect"))
    )
    (net (code "34") (name "unconnected-(U1-CLK-Pad38)") (class "Default")
      (node (ref "U1") (pin "38") (pinfunction "CLK_38") (pintype "unspecified+no_connect"))
    )
    (net (code "35") (name "unconnected-(U1-CMD-Pad18)") (class "Default")
      (node (ref "U1") (pin "18") (pinfunction "CMD_18") (pintype "unspecified+no_connect"))
    )
    (net (code "36") (name "unconnected-(U1-D0-Pad37)") (class "Default")
      (node (ref "U1") (pin "37") (pinfunction "D0_37") (pintype "unspecified+no_connect"))
    )
    (net (code "37") (name "unconnected-(U1-D1-Pad36)") (class "Default")
      (node (ref "U1") (pin "36") (pinfunction "D1_36") (pintype "unspecified+no_connect"))
    )
    (net (code "38") (name "unconnected-(U1-D2-Pad16)") (class "Default")
      (node (ref "U1") (pin "16") (pinfunction "D2_16") (pintype "unspecified+no_connect"))
    )
    (net (code "39") (name "unconnected-(U1-D3-Pad17)") (class "Default")
      (node (ref "U1") (pin "17") (pinfunction "D3_17") (pintype "unspecified+no_connect"))
    )
    (net (code "40") (name "unconnected-(U1-EN-Pad2)") (class "Default")
      (node (ref "U1") (pin "2") (pinfunction "EN_2") (pintype "unspecified+no_connect"))
    )
    (net (code "41") (name "unconnected-(U1-IO0-Pad33)") (class "Default")
      (node (ref "U1") (pin "33") (pinfunction "IO0_33") (pintype "unspecified+no_connect"))
    )
    (net (code "42") (name "unconnected-(U1-IO2-Pad34)") (class "Default")
      (node (ref "U1") (pin "34") (pinfunction "IO2_34") (pintype "unspecified+no_connect"))
    )
    (net (code "43") (name "unconnected-(U1-IO5-Pad29)") (class "Default")
      (node (ref "U1") (pin "29") (pinfunction "IO5_29") (pintype "unspecified+no_connect"))
    )
    (net (code "44") (name "unconnected-(U1-IO12-Pad13)") (class "Default")
      (node (ref "U1") (pin "13") (pinfunction "IO12_13") (pintype "unspecified+no_connect"))
    )
    (net (code "45") (name "unconnected-(U1-IO13-Pad15)") (class "Default")
      (node (ref "U1") (pin "15") (pinfunction "IO13_15") (pintype "unspecified"))
    )
    (net (code "46") (name "unconnected-(U1-IO14-Pad12)") (class "Default")
      (node (ref "U1") (pin "12") (pinfunction "IO14_12") (pintype "unspecified+no_connect"))
    )
    (net (code "47") (name "unconnected-(U1-IO16-Pad31)") (class "Default")
      (node (ref "U1") (pin "31") (pinfunction "IO16_31") (pintype "unspecified+no_connect"))
    )
    (net (code "48") (name "unconnected-(U1-IO17-Pad30)") (class "Default")
      (node (ref "U1") (pin "30") (pinfunction "IO17_30") (pintype "unspecified+no_connect"))
    )
    (net (code "49") (name "unconnected-(U1-RX-Pad24)") (class "Default")
      (node (ref "U1") (pin "24") (pinfunction "RX_24") (pintype "unspecified+no_connect"))
    )
    (net (code "50") (name "unconnected-(U1-TX-Pad23)") (class "Default")
      (node (ref "U1") (pin "23") (pinfunction "TX_23") (pintype "unspecified+no_connect"))
    )
    (net (code "51") (name "unconnected-(VEML-Pad2)") (class "Default")
      (node (ref "VEML") (pin "2") (pinfunction "2_2") (pintype "unspecified+no_connect"))
    )
  )
)
